# Sheet2.net
KiCad netlist of a schematic drawn in Altium Designer
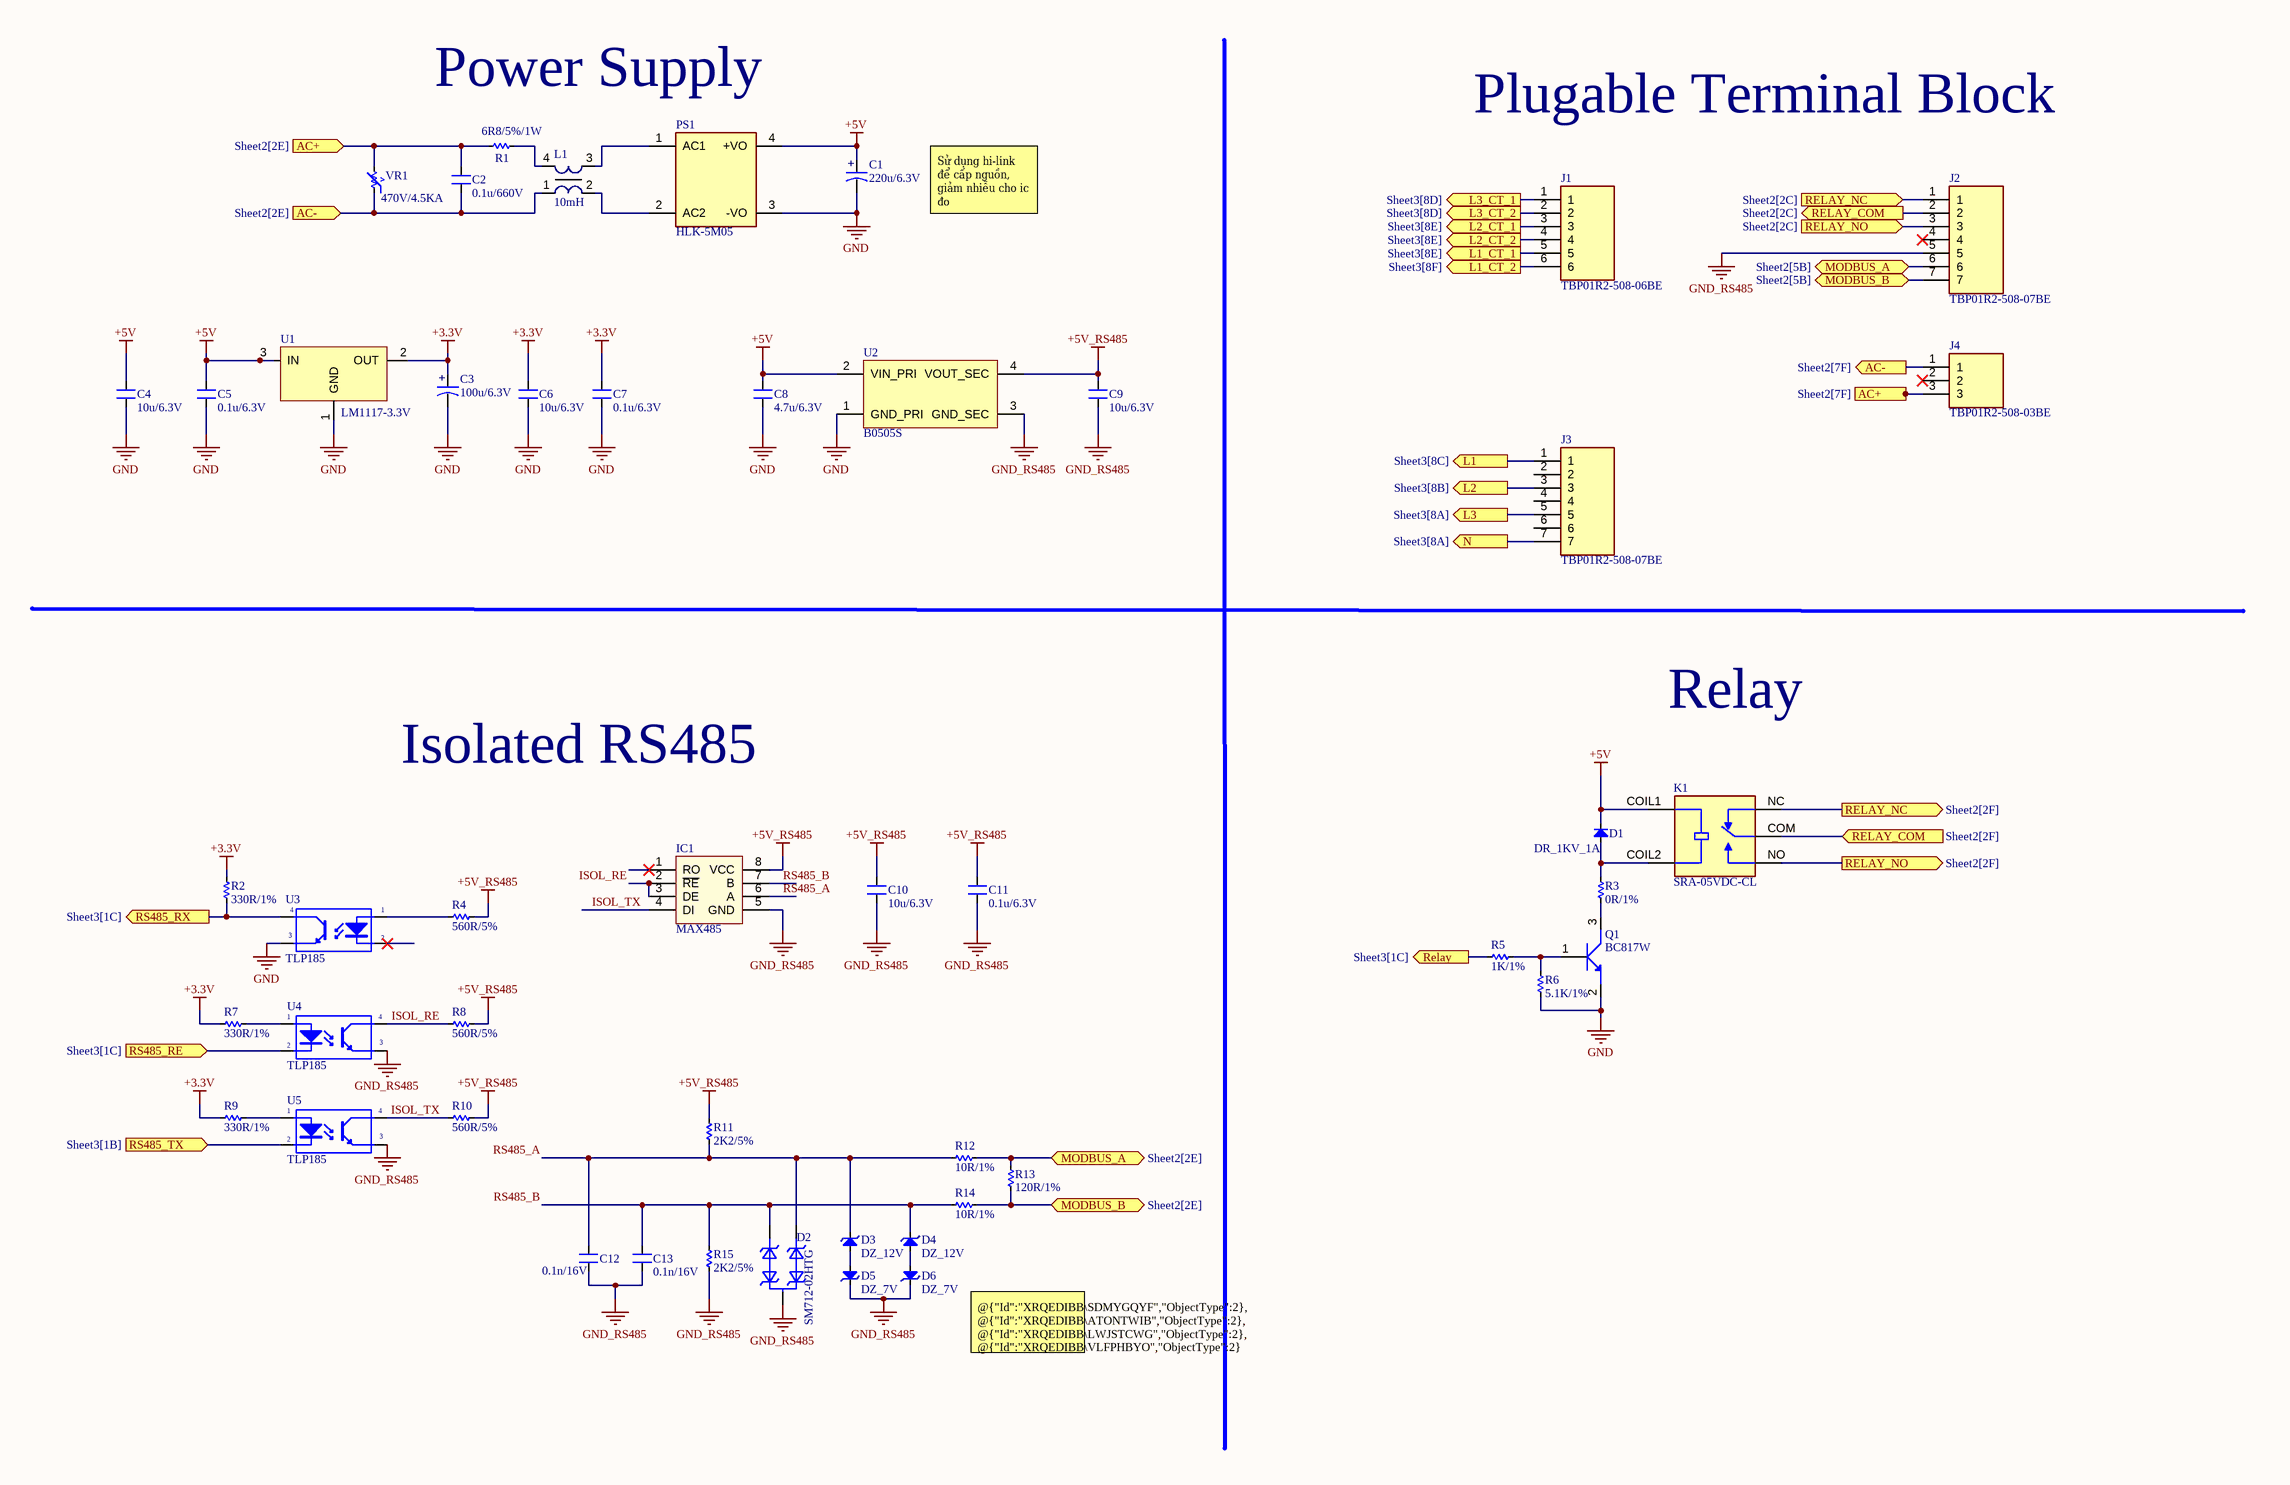
[diagram p0: Sheet2.SchDoc]

(export (version "E")
  (design (tool "Eeschema 10.0.6"))
  (components
    (comp (ref "C1")
      (value "220u/6.3V")
      (footprint "CAP-ALU-SMD-6.3x7.7x2.2")
      (libsource (lib "PowerMeter") (part "CAP_POLAR"))
    )
    (comp (ref "C2")
      (value "0.1u/660V")
      (footprint "CAPRR1500W60L1750T900H1600")
      (libsource (lib "DAK_Altium_Integrated_Lib") (part "CAP_SMD"))
    )
    (comp (ref "C3")
      (value "100u/6.3V")
      (footprint "CAP-ALU-SMD-6.3x7.7x2.2")
      (libsource (lib "PowerMeter") (part "CAP_POLAR"))
    )
    (comp (ref "C4")
      (value "10u/6.3V")
      (footprint "CAP_C_2012X110")
      (libsource (lib "DAK_Altium_Integrated_Lib") (part "CAP_SMD"))
    )
    (comp (ref "C5")
      (value "0.1u/6.3V")
      (footprint "CAP_C_2012X110")
      (libsource (lib "DAK_Altium_Integrated_Lib") (part "CAP_SMD"))
    )
    (comp (ref "C6")
      (value "10u/6.3V")
      (footprint "CAP_C_2012X110")
      (libsource (lib "DAK_Altium_Integrated_Lib") (part "CAP_SMD"))
    )
    (comp (ref "C7")
      (value "0.1u/6.3V")
      (footprint "CAP_C_2012X110")
      (libsource (lib "DAK_Altium_Integrated_Lib") (part "CAP_SMD"))
    )
    (comp (ref "C8")
      (value "4.7u/6.3V")
      (footprint "CAP_C_2012X110")
      (libsource (lib "DAK_Altium_Integrated_Lib") (part "CAP_SMD"))
    )
    (comp (ref "C9")
      (value "10u/6.3V")
      (footprint "CAP_C_2012X110")
      (libsource (lib "DAK_Altium_Integrated_Lib") (part "CAP_SMD"))
    )
    (comp (ref "C10")
      (value "10u/6.3V")
      (footprint "CAP_C_2012X110")
      (libsource (lib "DAK_Altium_Integrated_Lib") (part "CAP_SMD"))
    )
    (comp (ref "C11")
      (value "0.1u/6.3V")
      (footprint "CAP_C_2012X110")
      (libsource (lib "DAK_Altium_Integrated_Lib") (part "CAP_SMD"))
    )
    (comp (ref "C12")
      (value "0.1n/16V")
      (footprint "CAP_C_2012X110")
      (libsource (lib "DAK_Altium_Integrated_Lib") (part "CAP_SMD"))
    )
    (comp (ref "C13")
      (value "0.1n/16V")
      (footprint "CAP_C_2012X110")
      (libsource (lib "DAK_Altium_Integrated_Lib") (part "CAP_SMD"))
    )
    (comp (ref "D1")
      (value "DR_1KV_1A")
      (footprint "DIOM5025X26N")
      (description "Default Diode")
      (fields (field (name "PUBLISHER") "Altium Limited"))
      (libsource (lib "Library") (part "Diode"))
    )
    (comp (ref "D2")
      (value "SM712-02HTG")
      (footprint "SOT95P237X112-3N")
      (fields (field (name "MF") "Littelfuse Inc."))
      (libsource (lib "PowerMeter") (part "SM712-02HTG"))
    )
    (comp (ref "D3")
      (value "DZ_12V")
      (footprint "LL-34")
      (description "Zenner")
      (libsource (lib "PowerMeter") (part "DIODE Zener"))
    )
    (comp (ref "D4")
      (value "DZ_12V")
      (footprint "LL-34")
      (description "Zenner")
      (libsource (lib "PowerMeter") (part "DIODE Zener"))
    )
    (comp (ref "D5")
      (value "DZ_7V")
      (footprint "LL-34")
      (description "Zenner")
      (libsource (lib "PowerMeter") (part "DIODE Zener"))
    )
    (comp (ref "D6")
      (value "DZ_7V")
      (footprint "LL-34")
      (description "Zenner")
      (libsource (lib "PowerMeter") (part "DIODE Zener"))
    )
    (comp (ref "IC1")
      (value "MAX485")
      (footprint "SOIC-8")
      (description "RS232 - RS485 (Same sn75176)")
      (libsource (lib "PowerMeter") (part "MAX485"))
    )
    (comp (ref "J1")
      (value "TBP01R2-508-06BE")
      (footprint "CUI_TBP01R2-508-06BE")
      (fields (field (name "MF") "Same Sky"))
      (libsource (lib "PowerMeter") (part "TBP01R2-508-06BE"))
    )
    (comp (ref "J2")
      (value "TBP01R2-508-07BE")
      (footprint "CUI_TBP01R2-508-07BE")
      (description "2~24 Poles, Pluggable, Receptacle, Vertical, 5.08 Pitch, Terminal Block Connector")
      (fields (field (name "MF") "Same Sky"))
      (libsource (lib "PowerMeter") (part "TBP01R2-508-07BE"))
    )
    (comp (ref "J3")
      (value "TBP01R2-508-07BE")
      (footprint "CUI_TBP01R2-508-07BE")
      (description "2~24 Poles, Pluggable, Receptacle, Vertical, 5.08 Pitch, Terminal Block Connector")
      (fields (field (name "MF") "Same Sky"))
      (libsource (lib "PowerMeter") (part "TBP01R2-508-07BE"))
    )
    (comp (ref "J4")
      (value "TBP01R2-508-03BE")
      (footprint "CUI_TBP01R2-508-03BE")
      (description "2~24 Poles, Pluggable, Receptacle, Vertical, 5.08 Pitch, Terminal Block Connector")
      (fields (field (name "MF") "Same Sky"))
      (libsource (lib "PowerMeter") (part "TBP01R2-508-03BE"))
    )
    (comp (ref "K1")
      (value "SRA-05VDC-CL")
      (footprint "RELAY_SRA-05VDC-CL")
      (fields (field (name "MF") "Songle Relay"))
      (libsource (lib "PowerMeter") (part "SRA-05VDC-CL"))
    )
    (comp (ref "L1")
      (value "10mH")
      (footprint "UU98LFH142LF")
      (fields
        (field (name "PARTNO") "744284100")
        (field (name "MANUFACTURER") "Würth Elektronik eiSos GmbH")
        (field (name "CREATED BY") "Christin Zierenner")
      )
      (libsource (lib "Library") (part "L-DIP-2"))
    )
    (comp (ref "PS1")
      (value "HLK-5M05")
      (footprint "CONV_HLK-5M05")
      (description "AC DC 220V to 5V 5W 5Watt Isolated Switching Step-Down Power Supply Module Converter")
      (fields (field (name "MF") "Hi-link"))
      (libsource (lib "PowerMeter") (part "HLK-5M05"))
    )
    (comp (ref "Q1")
      (value "BC817W")
      (footprint "SOT95P237X112-3N")
      (libsource (lib "PowerMeter") (part "BJT_NPN"))
    )
    (comp (ref "R1")
      (value "6R8/5%/1W")
      (footprint "RES-1W")
      (description "Resistor")
      (fields
        (field (name "MANUFACTURER") "Generic Components")
        (field (name "PUBLISHER") "Altium Hobart Technology Centre")
      )
      (libsource (lib "Library") (part "Res-SMD"))
    )
    (comp (ref "R2")
      (value "330R/1%")
      (footprint "RES_C_2012X65")
      (description "Resistor")
      (fields
        (field (name "MANUFACTURER") "Generic Components")
        (field (name "PUBLISHER") "Altium Hobart Technology Centre")
      )
      (libsource (lib "Library") (part "Res-SMD"))
    )
    (comp (ref "R3")
      (value "0R/1%")
      (footprint "RES_C_2012X65")
      (description "Resistor")
      (fields
        (field (name "MANUFACTURER") "Generic Components")
        (field (name "PUBLISHER") "Altium Hobart Technology Centre")
      )
      (libsource (lib "Library") (part "Res-SMD"))
    )
    (comp (ref "R4")
      (value "560R/5%")
      (footprint "RES_C_2012X65")
      (description "Resistor")
      (fields
        (field (name "MANUFACTURER") "Generic Components")
        (field (name "PUBLISHER") "Altium Hobart Technology Centre")
      )
      (libsource (lib "Library") (part "Res-SMD"))
    )
    (comp (ref "R5")
      (value "1K/1%")
      (footprint "RES_C_2012X65")
      (description "Resistor")
      (fields
        (field (name "MANUFACTURER") "Generic Components")
        (field (name "PUBLISHER") "Altium Hobart Technology Centre")
      )
      (libsource (lib "Library") (part "Res-SMD"))
    )
    (comp (ref "R6")
      (value "5.1K/1%")
      (footprint "RES_C_2012X65")
      (description "Resistor")
      (fields
        (field (name "MANUFACTURER") "Generic Components")
        (field (name "PUBLISHER") "Altium Hobart Technology Centre")
      )
      (libsource (lib "Library") (part "Res-SMD"))
    )
    (comp (ref "R7")
      (value "330R/1%")
      (footprint "RES_C_2012X65")
      (description "Resistor")
      (fields
        (field (name "MANUFACTURER") "Generic Components")
        (field (name "PUBLISHER") "Altium Hobart Technology Centre")
      )
      (libsource (lib "Library") (part "Res-SMD"))
    )
    (comp (ref "R8")
      (value "560R/5%")
      (footprint "RES_C_2012X65")
      (description "Resistor")
      (fields
        (field (name "MANUFACTURER") "Generic Components")
        (field (name "PUBLISHER") "Altium Hobart Technology Centre")
      )
      (libsource (lib "Library") (part "Res-SMD"))
    )
    (comp (ref "R9")
      (value "330R/1%")
      (footprint "RES_C_2012X65")
      (description "Resistor")
      (fields
        (field (name "MANUFACTURER") "Generic Components")
        (field (name "PUBLISHER") "Altium Hobart Technology Centre")
      )
      (libsource (lib "Library") (part "Res-SMD"))
    )
    (comp (ref "R10")
      (value "560R/5%")
      (footprint "RES_C_2012X65")
      (description "Resistor")
      (fields
        (field (name "MANUFACTURER") "Generic Components")
        (field (name "PUBLISHER") "Altium Hobart Technology Centre")
      )
      (libsource (lib "Library") (part "Res-SMD"))
    )
    (comp (ref "R11")
      (value "2K2/5%")
      (footprint "RES_C_2012X65")
      (description "Resistor")
      (fields
        (field (name "MANUFACTURER") "Generic Components")
        (field (name "PUBLISHER") "Altium Hobart Technology Centre")
      )
      (libsource (lib "Library") (part "Res-SMD"))
    )
    (comp (ref "R12")
      (value "10R/1%")
      (footprint "RES_C_3216X70")
      (description "Resistor")
      (fields
        (field (name "MANUFACTURER") "Generic Components")
        (field (name "PUBLISHER") "Altium Hobart Technology Centre")
      )
      (libsource (lib "Library") (part "Res-SMD"))
    )
    (comp (ref "R13")
      (value "120R/1%")
      (footprint "RES_C_3216X70")
      (description "Resistor")
      (fields
        (field (name "MANUFACTURER") "Generic Components")
        (field (name "PUBLISHER") "Altium Hobart Technology Centre")
      )
      (libsource (lib "Library") (part "Res-SMD"))
    )
    (comp (ref "R14")
      (value "10R/1%")
      (footprint "RES_C_3216X70")
      (description "Resistor")
      (fields
        (field (name "MANUFACTURER") "Generic Components")
        (field (name "PUBLISHER") "Altium Hobart Technology Centre")
      )
      (libsource (lib "Library") (part "Res-SMD"))
    )
    (comp (ref "R15")
      (value "2K2/5%")
      (footprint "RES_C_2012X65")
      (description "Resistor")
      (fields
        (field (name "MANUFACTURER") "Generic Components")
        (field (name "PUBLISHER") "Altium Hobart Technology Centre")
      )
      (libsource (lib "Library") (part "Res-SMD"))
    )
    (comp (ref "U1")
      (value "LM1117-3.3V")
      (footprint "SOT230P700X180-4N")
      (description "800mA Low-Dropout Linear Regulator")
      (fields (field (name "CREATOR") "Nguyen Ba Bien"))
      (libsource (lib "PowerMeter") (part "LM1117"))
    )
    (comp (ref "U2") (value "B0505S") (footprint "B0505S-1W") (libsource (lib "PowerMeter") (part "B0505S")))
    (comp (ref "U3")
      (value "TLP185")
      (footprint "SOP254P700X220-4N")
      (description "Single Opto")
      (libsource (lib "PowerMeter") (part "TLP185"))
    )
    (comp (ref "U4")
      (value "TLP185")
      (footprint "SOP254P700X220-4N")
      (description "Single Opto")
      (libsource (lib "PowerMeter") (part "TLP185"))
    )
    (comp (ref "U5")
      (value "TLP185")
      (footprint "SOP254P700X220-4N")
      (description "Single Opto")
      (libsource (lib "PowerMeter") (part "TLP185"))
    )
    (comp (ref "VR1")
      (value "470V/4.5KA")
      (footprint "B72214P2301K101")
      (description "MOV-14D471K, Varistors 470V 14mm")
      (libsource (lib "PowerMeter") (part "Varistor"))
    )
  )
  (nets
    (net (code "1") (name "+3.3V") (class "Default")
      (node (ref "C3") (pin "1") (pinfunction "1_1") (pintype "passive"))
      (node (ref "C6") (pin "2") (pinfunction "2_2") (pintype "passive"))
      (node (ref "C7") (pin "2") (pinfunction "2_2") (pintype "passive"))
      (node (ref "R2") (pin "1") (pinfunction "1_1") (pintype "passive"))
      (node (ref "R7") (pin "1") (pinfunction "1_1") (pintype "passive"))
      (node (ref "R9") (pin "1") (pinfunction "1_1") (pintype "passive"))
      (node (ref "U1") (pin "2") (pinfunction "OUT_2") (pintype "passive"))
    )
    (net (code "2") (name "+5V") (class "Default")
      (node (ref "C1") (pin "1") (pinfunction "1_1") (pintype "passive"))
      (node (ref "C4") (pin "2") (pinfunction "2_2") (pintype "passive"))
      (node (ref "C5") (pin "2") (pinfunction "2_2") (pintype "passive"))
      (node (ref "C8") (pin "2") (pinfunction "2_2") (pintype "passive"))
      (node (ref "D1") (pin "2") (pinfunction "K_2") (pintype "passive"))
      (node (ref "K1") (pin "COIL1") (pinfunction "COIL1_COIL1") (pintype "passive"))
      (node (ref "PS1") (pin "4") (pinfunction "+VO_4") (pintype "passive"))
      (node (ref "U1") (pin "3") (pinfunction "IN_3") (pintype "passive"))
      (node (ref "U2") (pin "2") (pinfunction "VIN_PRI_2") (pintype "passive"))
    )
    (net (code "3") (name "+5V_RS485") (class "Default")
      (node (ref "C10") (pin "2") (pinfunction "2_2") (pintype "passive"))
      (node (ref "C11") (pin "2") (pinfunction "2_2") (pintype "passive"))
      (node (ref "C9") (pin "2") (pinfunction "2_2") (pintype "passive"))
      (node (ref "IC1") (pin "8") (pinfunction "VCC_8") (pintype "passive"))
      (node (ref "R10") (pin "2") (pinfunction "2_2") (pintype "passive"))
      (node (ref "R11") (pin "2") (pinfunction "2_2") (pintype "passive"))
      (node (ref "R4") (pin "2") (pinfunction "2_2") (pintype "passive"))
      (node (ref "R8") (pin "2") (pinfunction "2_2") (pintype "passive"))
      (node (ref "U2") (pin "4") (pinfunction "VOUT_SEC_4") (pintype "passive"))
    )
    (net (code "4") (name "/AC+") (class "Default")
      (node (ref "C2") (pin "2") (pinfunction "2_2") (pintype "passive"))
      (node (ref "J4") (pin "3") (pinfunction "3_3") (pintype "passive"))
      (node (ref "R1") (pin "1") (pinfunction "1_1") (pintype "passive"))
      (node (ref "VR1") (pin "1") (pinfunction "1_1") (pintype "passive"))
    )
    (net (code "5") (name "/AC-") (class "Default")
      (node (ref "C2") (pin "1") (pinfunction "1_1") (pintype "passive"))
      (node (ref "J4") (pin "1") (pinfunction "1_1") (pintype "passive"))
      (node (ref "L1") (pin "1") (pinfunction "1_1") (pintype "passive"))
      (node (ref "VR1") (pin "2") (pinfunction "2_2") (pintype "passive"))
    )
    (net (code "6") (name "/ISOL_RE") (class "Default")
      (node (ref "IC1") (pin "2") (pinfunction "~{RE}_2") (pintype "passive"))
      (node (ref "IC1") (pin "3") (pinfunction "DE_3") (pintype "passive"))
      (node (ref "R8") (pin "1") (pinfunction "1_1") (pintype "passive"))
      (node (ref "U4") (pin "4") (pinfunction "C_4") (pintype "passive"))
    )
    (net (code "7") (name "/ISOL_TX") (class "Default")
      (node (ref "IC1") (pin "4") (pinfunction "DI_4") (pintype "passive"))
      (node (ref "R10") (pin "1") (pinfunction "1_1") (pintype "passive"))
      (node (ref "U5") (pin "4") (pinfunction "C_4") (pintype "passive"))
    )
    (net (code "8") (name "/L1") (class "Default")
      (node (ref "J3") (pin "1") (pinfunction "1_1") (pintype "passive"))
    )
    (net (code "9") (name "/L1_CT_1") (class "Default")
      (node (ref "J1") (pin "5") (pinfunction "5_5") (pintype "passive"))
    )
    (net (code "10") (name "/L1_CT_2") (class "Default")
      (node (ref "J1") (pin "6") (pinfunction "6_6") (pintype "passive"))
    )
    (net (code "11") (name "/L2") (class "Default")
      (node (ref "J3") (pin "3") (pinfunction "3_3") (pintype "passive"))
    )
    (net (code "12") (name "/L2_CT_1") (class "Default")
      (node (ref "J1") (pin "3") (pinfunction "3_3") (pintype "passive"))
    )
    (net (code "13") (name "/L2_CT_2") (class "Default")
      (node (ref "J1") (pin "4") (pinfunction "4_4") (pintype "passive"))
    )
    (net (code "14") (name "/L3") (class "Default")
      (node (ref "J3") (pin "5") (pinfunction "5_5") (pintype "passive"))
    )
    (net (code "15") (name "/L3_CT_1") (class "Default")
      (node (ref "J1") (pin "1") (pinfunction "1_1") (pintype "passive"))
    )
    (net (code "16") (name "/L3_CT_2") (class "Default")
      (node (ref "J1") (pin "2") (pinfunction "2_2") (pintype "passive"))
    )
    (net (code "17") (name "/MODBUS_A") (class "Default")
      (node (ref "J2") (pin "6") (pinfunction "6_6") (pintype "passive"))
      (node (ref "R12") (pin "2") (pinfunction "2_2") (pintype "passive"))
      (node (ref "R13") (pin "2") (pinfunction "2_2") (pintype "passive"))
    )
    (net (code "18") (name "/MODBUS_B") (class "Default")
      (node (ref "J2") (pin "7") (pinfunction "7_7") (pintype "passive"))
      (node (ref "R13") (pin "1") (pinfunction "1_1") (pintype "passive"))
      (node (ref "R14") (pin "2") (pinfunction "2_2") (pintype "passive"))
    )
    (net (code "19") (name "/N") (class "Default")
      (node (ref "J3") (pin "7") (pinfunction "7_7") (pintype "passive"))
    )
    (net (code "20") (name "/RELAY_COM") (class "Default")
      (node (ref "J2") (pin "2") (pinfunction "2_2") (pintype "passive"))
      (node (ref "K1") (pin "COM") (pinfunction "COM_COM") (pintype "passive"))
    )
    (net (code "21") (name "/RELAY_NC") (class "Default")
      (node (ref "J2") (pin "1") (pinfunction "1_1") (pintype "passive"))
      (node (ref "K1") (pin "NC") (pinfunction "NC_NC") (pintype "passive"))
    )
    (net (code "22") (name "/RELAY_NO") (class "Default")
      (node (ref "J2") (pin "3") (pinfunction "3_3") (pintype "passive"))
      (node (ref "K1") (pin "NO") (pinfunction "NO_NO") (pintype "passive"))
    )
    (net (code "23") (name "/RS485_A") (class "Default")
      (node (ref "C12") (pin "2") (pinfunction "2_2") (pintype "passive"))
      (node (ref "D2") (pin "1") (pinfunction "1_1") (pintype "passive"))
      (node (ref "D3") (pin "1") (pinfunction "K_1") (pintype "passive"))
      (node (ref "IC1") (pin "6") (pinfunction "A_6") (pintype "passive"))
      (node (ref "R11") (pin "1") (pinfunction "1_1") (pintype "passive"))
      (node (ref "R12") (pin "1") (pinfunction "1_1") (pintype "passive"))
    )
    (net (code "24") (name "/RS485_B") (class "Default")
      (node (ref "C13") (pin "2") (pinfunction "2_2") (pintype "passive"))
      (node (ref "D2") (pin "2") (pinfunction "2_2") (pintype "passive"))
      (node (ref "D4") (pin "1") (pinfunction "K_1") (pintype "passive"))
      (node (ref "IC1") (pin "7") (pinfunction "B_7") (pintype "passive"))
      (node (ref "R14") (pin "1") (pinfunction "1_1") (pintype "passive"))
      (node (ref "R15") (pin "2") (pinfunction "2_2") (pintype "passive"))
    )
    (net (code "25") (name "/RS485_RE") (class "Default")
      (node (ref "U4") (pin "2") (pinfunction "K_2") (pintype "passive"))
    )
    (net (code "26") (name "/RS485_RX") (class "Default")
      (node (ref "R2") (pin "2") (pinfunction "2_2") (pintype "passive"))
      (node (ref "U3") (pin "4") (pinfunction "C_4") (pintype "passive"))
    )
    (net (code "27") (name "/RS485_TX") (class "Default")
      (node (ref "U5") (pin "2") (pinfunction "K_2") (pintype "passive"))
    )
    (net (code "28") (name "/Relay") (class "Default")
      (node (ref "R5") (pin "1") (pinfunction "1_1") (pintype "passive"))
    )
    (net (code "29") (name "GND") (class "Default")
      (node (ref "C1") (pin "2") (pinfunction "2_2") (pintype "passive"))
      (node (ref "C3") (pin "2") (pinfunction "2_2") (pintype "passive"))
      (node (ref "C4") (pin "1") (pinfunction "1_1") (pintype "passive"))
      (node (ref "C5") (pin "1") (pinfunction "1_1") (pintype "passive"))
      (node (ref "C6") (pin "1") (pinfunction "1_1") (pintype "passive"))
      (node (ref "C7") (pin "1") (pinfunction "1_1") (pintype "passive"))
      (node (ref "C8") (pin "1") (pinfunction "1_1") (pintype "passive"))
      (node (ref "PS1") (pin "3") (pinfunction "-VO_3") (pintype "passive"))
      (node (ref "Q1") (pin "2") (pinfunction "E_2") (pintype "passive"))
      (node (ref "R6") (pin "1") (pinfunction "1_1") (pintype "passive"))
      (node (ref "U1") (pin "1") (pinfunction "GND_1") (pintype "passive"))
      (node (ref "U2") (pin "1") (pinfunction "GND_PRI_1") (pintype "passive"))
      (node (ref "U3") (pin "3") (pinfunction "E_3") (pintype "passive"))
    )
    (net (code "30") (name "GND_RS485") (class "Default")
      (node (ref "C10") (pin "1") (pinfunction "1_1") (pintype "passive"))
      (node (ref "C11") (pin "1") (pinfunction "1_1") (pintype "passive"))
      (node (ref "C12") (pin "1") (pinfunction "1_1") (pintype "passive"))
      (node (ref "C13") (pin "1") (pinfunction "1_1") (pintype "passive"))
      (node (ref "C9") (pin "1") (pinfunction "1_1") (pintype "passive"))
      (node (ref "D2") (pin "3") (pinfunction "3_3") (pintype "passive"))
      (node (ref "D5") (pin "1") (pinfunction "K_1") (pintype "passive"))
      (node (ref "D6") (pin "1") (pinfunction "K_1") (pintype "passive"))
      (node (ref "IC1") (pin "5") (pinfunction "GND_5") (pintype "passive"))
      (node (ref "J2") (pin "5") (pinfunction "5_5") (pintype "passive"))
      (node (ref "R15") (pin "1") (pinfunction "1_1") (pintype "passive"))
      (node (ref "U2") (pin "3") (pinfunction "GND_SEC_3") (pintype "passive"))
      (node (ref "U4") (pin "3") (pinfunction "E_3") (pintype "passive"))
      (node (ref "U5") (pin "3") (pinfunction "E_3") (pintype "passive"))
    )
    (net (code "31") (name "Net-(D1-A)") (class "Default")
      (node (ref "D1") (pin "1") (pinfunction "A_1") (pintype "passive"))
      (node (ref "K1") (pin "COIL2") (pinfunction "COIL2_COIL2") (pintype "passive"))
      (node (ref "R3") (pin "2") (pinfunction "2_2") (pintype "passive"))
    )
    (net (code "32") (name "Net-(D3-A)") (class "Default")
      (node (ref "D3") (pin "2") (pinfunction "A_2") (pintype "passive"))
      (node (ref "D5") (pin "2") (pinfunction "A_2") (pintype "passive"))
    )
    (net (code "33") (name "Net-(D4-A)") (class "Default")
      (node (ref "D4") (pin "2") (pinfunction "A_2") (pintype "passive"))
      (node (ref "D6") (pin "2") (pinfunction "A_2") (pintype "passive"))
    )
    (net (code "34") (name "Net-(L1-Pad4)") (class "Default")
      (node (ref "L1") (pin "4") (pinfunction "4_4") (pintype "passive"))
      (node (ref "R1") (pin "2") (pinfunction "2_2") (pintype "passive"))
    )
    (net (code "35") (name "Net-(PS1-AC1)") (class "Default")
      (node (ref "L1") (pin "3") (pinfunction "3_3") (pintype "passive"))
      (node (ref "PS1") (pin "1") (pinfunction "AC1_1") (pintype "passive"))
    )
    (net (code "36") (name "Net-(PS1-AC2)") (class "Default")
      (node (ref "L1") (pin "2") (pinfunction "2_2") (pintype "passive"))
      (node (ref "PS1") (pin "2") (pinfunction "AC2_2") (pintype "passive"))
    )
    (net (code "37") (name "Net-(Q1-B)") (class "Default")
      (node (ref "Q1") (pin "1") (pinfunction "B_1") (pintype "passive"))
      (node (ref "R5") (pin "2") (pinfunction "2_2") (pintype "passive"))
      (node (ref "R6") (pin "2") (pinfunction "2_2") (pintype "passive"))
    )
    (net (code "38") (name "Net-(Q1-C)") (class "Default")
      (node (ref "Q1") (pin "3") (pinfunction "C_3") (pintype "passive"))
      (node (ref "R3") (pin "1") (pinfunction "1_1") (pintype "passive"))
    )
    (net (code "39") (name "Net-(U3-A)") (class "Default")
      (node (ref "R4") (pin "1") (pinfunction "1_1") (pintype "passive"))
      (node (ref "U3") (pin "1") (pinfunction "A_1") (pintype "passive"))
    )
    (net (code "40") (name "Net-(U4-A)") (class "Default")
      (node (ref "R7") (pin "2") (pinfunction "2_2") (pintype "passive"))
      (node (ref "U4") (pin "1") (pinfunction "A_1") (pintype "passive"))
    )
    (net (code "41") (name "Net-(U5-A)") (class "Default")
      (node (ref "R9") (pin "2") (pinfunction "2_2") (pintype "passive"))
      (node (ref "U5") (pin "1") (pinfunction "A_1") (pintype "passive"))
    )
    (net (code "42") (name "unconnected-(IC1-RO-Pad1)") (class "Default")
      (node (ref "IC1") (pin "1") (pinfunction "RO_1") (pintype "passive+no_connect"))
    )
    (net (code "43") (name "unconnected-(J2-Pad4)") (class "Default")
      (node (ref "J2") (pin "4") (pinfunction "4_4") (pintype "passive+no_connect"))
    )
    (net (code "44") (name "unconnected-(J3-Pad2)") (class "Default")
      (node (ref "J3") (pin "2") (pinfunction "2_2") (pintype "passive"))
    )
    (net (code "45") (name "unconnected-(J3-Pad4)") (class "Default")
      (node (ref "J3") (pin "4") (pinfunction "4_4") (pintype "passive"))
    )
    (net (code "46") (name "unconnected-(J3-Pad6)") (class "Default")
      (node (ref "J3") (pin "6") (pinfunction "6_6") (pintype "passive"))
    )
    (net (code "47") (name "unconnected-(J4-Pad2)") (class "Default")
      (node (ref "J4") (pin "2") (pinfunction "2_2") (pintype "passive+no_connect"))
    )
    (net (code "48") (name "unconnected-(U3-K-Pad2)") (class "Default")
      (node (ref "U3") (pin "2") (pinfunction "K_2") (pintype "passive+no_connect"))
    )
  )
)
